# Carte_MiniPAMI_2025.net
KiCad netlist of a schematic drawn in Altium Designer
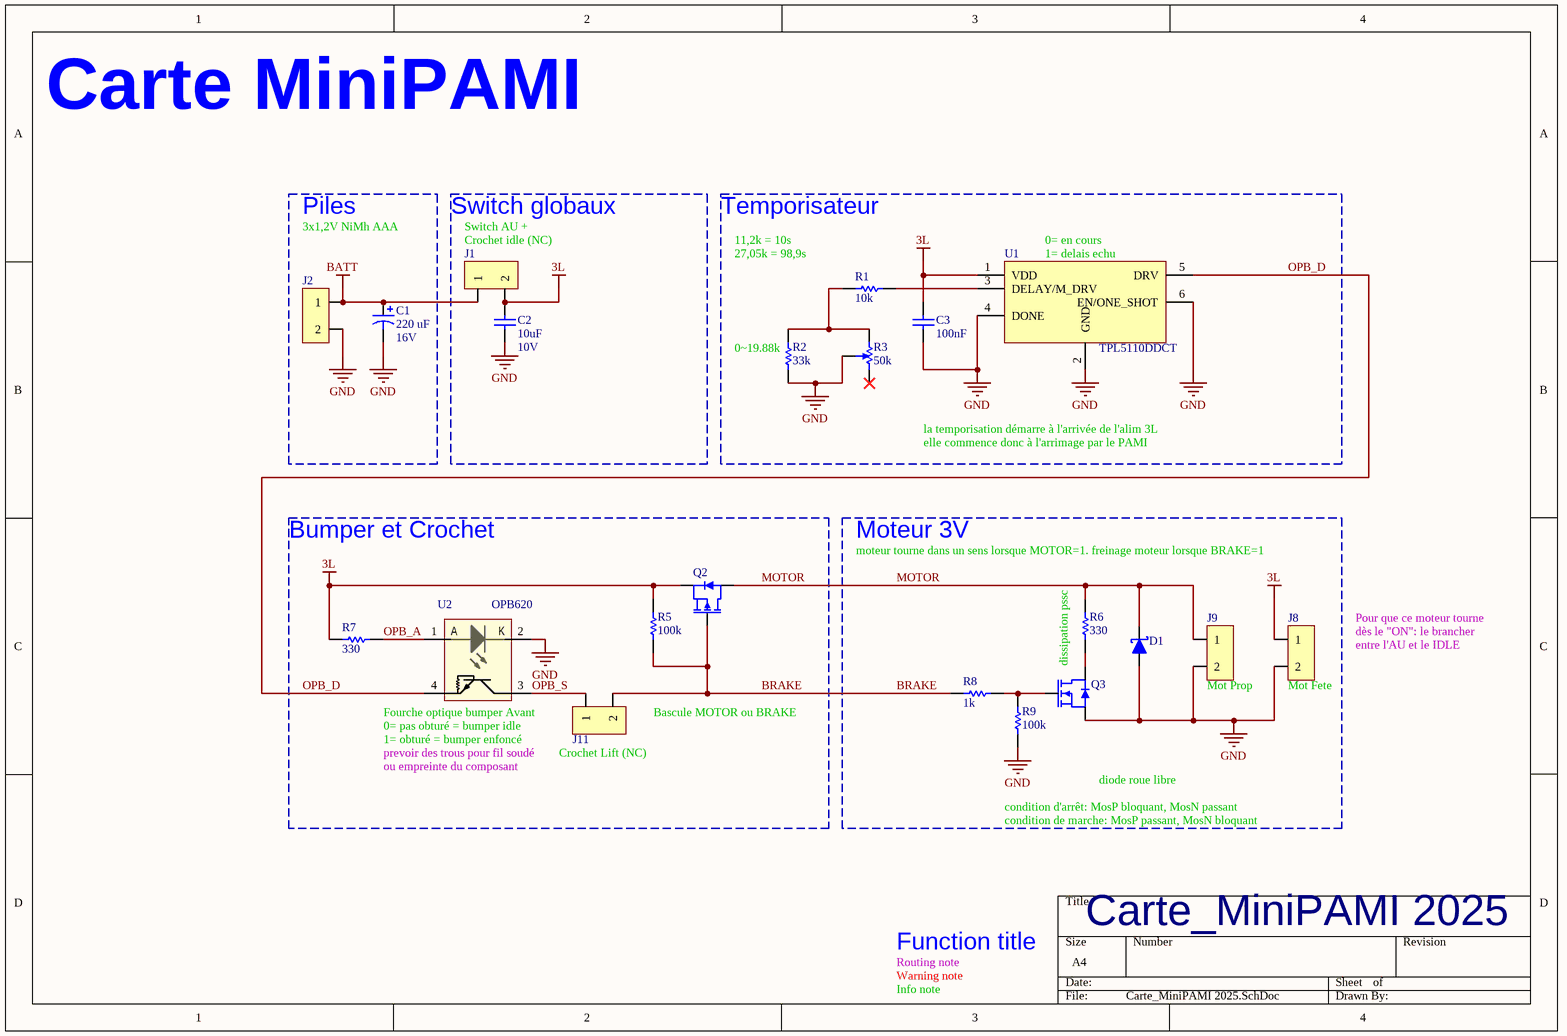
[diagram p0: Carte_MiniPAMI 2025.SchDoc]

(export (version "E")
  (design (tool "Eeschema 10.0.6"))
  (components
    (comp (ref "C1")
      (value "220 uF")
      (footprint "WCAP-ATG8_6.3x11x2.5x0.5")
      (description "CAP Alu 220 UF 20% 16 V")
      (fields
        (field (name "MANUFACTURER") "Wurth Elektronik")
        (field (name "MANUFACTURER PART NUMBER") "860010373010")
        (field (name "RATEDVOLTAGE") "16V")
      )
      (libsource (lib "Condensateur") (part "WCAP-ATG8, 860010373010"))
    )
    (comp (ref "C2")
      (value "10uF")
      (footprint "WCAP-CSGP_0805, 2x1.25x1.25")
      (description "CAP CER 10uF 10V X7R 0805")
      (fields
        (field (name "RATEDVOLTAGE") "10V")
        (field (name "MANUFACTURER") "Wurth Elektronik")
        (field (name "MANUFACTURER PART NUMBER") "885012207026")
      )
      (libsource (lib "Condensateur") (part "WCAP-CSGP, 885012207026"))
    )
    (comp (ref "C3")
      (value "100nF")
      (footprint "WCAP-CSGP_0603, 1.6x0.8x0.8")
      (description "CAP CER 100nF 50V X7R 0603")
      (fields
        (field (name "MANUFACTURER") "Wurth Elektronik")
        (field (name "MANUFACTURER PART NUMBER") "885012206095")
      )
      (libsource (lib "Condensateur") (part "WCAP-CSGP, 885012206095"))
    )
    (comp (ref "D1")
      (value "RBR3MM40ATFTR")
      (footprint "SOD-123FL")
      (description "DIODE SCHOTTKY 40V 3A SOD123-FL")
      (fields (field (name "MANUFACTURER") "ROHM"))
      (libsource (lib "Diode") (part "RBR3MM40ATFTR"))
    )
    (comp (ref "J1")
      (value "22-03-2021")
      (footprint "Conn_22-03-2021")
      (description "CONN HEADER VERT 2POS 2.54MM")
      (fields (field (name "MANUFACTURER") "MOLEX"))
      (libsource (lib "") (part "Conn_22-03-2021_1"))
    )
    (comp (ref "J2")
      (value "22-03-2021")
      (footprint "Conn_22-03-2021")
      (description "CONN HEADER VERT 2POS 2.54MM")
      (fields (field (name "MANUFACTURER") "MOLEX"))
      (libsource (lib "") (part "Conn_22-03-2021_3"))
    )
    (comp (ref "J8")
      (value "22-03-2021")
      (footprint "Conn_22-03-2021")
      (description "CONN HEADER VERT 2POS 2.54MM")
      (fields (field (name "MANUFACTURER") "MOLEX"))
      (libsource (lib "Connecteurs") (part "Conn_22-03-2021"))
    )
    (comp (ref "J9")
      (value "22-03-2021")
      (footprint "Conn_22-03-2021")
      (description "CONN HEADER VERT 2POS 2.54MM")
      (fields (field (name "MANUFACTURER") "MOLEX"))
      (libsource (lib "Connecteurs") (part "Conn_22-03-2021"))
    )
    (comp (ref "J11")
      (value "22-03-2021")
      (footprint "Conn_22-03-2021")
      (description "CONN HEADER VERT 2POS 2.54MM")
      (fields (field (name "MANUFACTURER") "MOLEX"))
      (libsource (lib "") (part "Conn_22-03-2021_2"))
    )
    (comp (ref "Q2")
      (value "ZXM61P03FTA")
      (footprint "SOT-23")
      (description "MOSFET P-CH 30V 1.1A SOT23-3")
      (fields (field (name "MANUFACTURER") "Diodes Incorporated"))
      (libsource (lib "Transistors") (part "ZXM61P03FTA"))
    )
    (comp (ref "Q3")
      (value "IRLML0040TRPBF")
      (footprint "SOT-23")
      (description "MOSFET N 40V 3.6A SOT23")
      (fields (field (name "MANUFACTURER") "INTERNATIONAL RECTIFIER"))
      (libsource (lib "Transistors") (part "IRLML0040"))
    )
    (comp (ref "R1")
      (value "10k")
      (footprint "RESC1608X06N")
      (description "RES SMD 10K OHM 1% 1/10W 0603")
      (fields
        (field (name "MANUFACTURER") "Yageo")
        (field (name "MANUFACTURER PART NUMBER") "RC0603FR-0710KL")
      )
      (libsource (lib "Resistance") (part "RC0603FR-0710KL"))
    )
    (comp (ref "R2")
      (value "33k")
      (footprint "RESC1608X06N")
      (description "RES SMD 33K OHM 1% 1/10W 0603")
      (fields (field (name "MANUFACTURER") "Yageo") (field (name "POWER") "100mW"))
      (libsource (lib "Resistance") (part "RC0603FR-0710KL"))
    )
    (comp (ref "R3")
      (value "50k")
      (footprint "TRIM_PANASONIC_EVM-2W")
      (description "TRIMMER 50K OHM 0.15W SMD")
      (fields
        (field (name "MANUFACTURER") "PANASONIC ELECTRONIC COMPONENTS")
        (field (name "MANUFACTURER PART NUMBER") "EVM2WSX80B54")
      )
      (libsource (lib "Resistance") (part "EVM2WSX80B54"))
    )
    (comp (ref "R5")
      (value "100k")
      (footprint "RESC1608X06N")
      (description "RES SMD 100K OHM 1% 1/10W 0603")
      (fields
        (field (name "MANUFACTURER") "Yageo")
        (field (name "MANUFACTURER PART NUMBER") "RC0603FR-07100KL")
      )
      (libsource (lib "Resistance") (part "RC0603FR-07100KL"))
    )
    (comp (ref "R6")
      (value "330")
      (footprint "RESC1608X06N")
      (description "RES SMD 330 OHM 1% 1/10W 0603")
      (fields
        (field (name "MANUFACTURER") "Yageo")
        (field (name "MANUFACTURER PART NUMBER") "RC0603FR-07330RL")
      )
      (libsource (lib "Resistance") (part "RC0603FR-07330RL"))
    )
    (comp (ref "R7")
      (value "330")
      (footprint "RESC1608X06N")
      (description "RES SMD 330 OHM 1% 1/10W 0603")
      (fields
        (field (name "MANUFACTURER") "Yageo")
        (field (name "MANUFACTURER PART NUMBER") "RC0603FR-07330RL")
      )
      (libsource (lib "Resistance") (part "RC0603FR-07330RL"))
    )
    (comp (ref "R8")
      (value "1k")
      (footprint "RESC1608X06N")
      (description "RES SMD 1K OHM 1% 1/10W 0603")
      (fields
        (field (name "MANUFACTURER") "Yageo")
        (field (name "MANUFACTURER PART NUMBER") "RC0603FR-071KL")
      )
      (libsource (lib "Resistance") (part "RC0603FR-071KL"))
    )
    (comp (ref "R9")
      (value "100k")
      (footprint "RESC1608X06N")
      (description "RES SMD 100K OHM 1% 1/10W 0603")
      (fields
        (field (name "MANUFACTURER") "Yageo")
        (field (name "MANUFACTURER PART NUMBER") "RC0603FR-07100KL")
      )
      (libsource (lib "Resistance") (part "RC0603FR-07100KL"))
    )
    (comp (ref "U1")
      (value "TPL5110DDCT")
      (footprint "SOT23_95P280X145-6N")
      (description "IC OSC PROG TIMER TSOT23-6")
      (fields (field (name "MANUFACTURER") "TEXAS INSTRUMENTS"))
      (libsource (lib "CI") (part "TPL5110DDCT"))
    )
    (comp (ref "U2")
      (value "OPB620")
      (footprint "OPB620")
      (description "SENSOR OPT SLOT TRANS W/RES PCB")
      (fields (field (name "MANUFACTURER") "TT ELECTRONICS"))
      (libsource (lib "Opto") (part "OPB620"))
    )
  )
  (nets
    (net (code "1") (name "/BRAKE") (class "Default")
      (node (ref "J11") (pin "2") (pinfunction "2_2") (pintype "passive"))
      (node (ref "Q2") (pin "1") (pinfunction "G_1") (pintype "passive"))
      (node (ref "R5") (pin "1") (pinfunction "1_1") (pintype "passive"))
      (node (ref "R8") (pin "2") (pinfunction "2_2") (pintype "passive"))
    )
    (net (code "2") (name "/MOTOR") (class "Default")
      (node (ref "D1") (pin "2") (pintype "passive"))
      (node (ref "J9") (pin "1") (pinfunction "1_1") (pintype "passive"))
      (node (ref "Q2") (pin "3") (pinfunction "D_3") (pintype "passive"))
      (node (ref "R6") (pin "2") (pinfunction "2_2") (pintype "passive"))
    )
    (net (code "3") (name "/OPB_A") (class "Default")
      (node (ref "R7") (pin "2") (pinfunction "2_2") (pintype "passive"))
      (node (ref "U2") (pin "1") (pinfunction "LED_A_1") (pintype "passive"))
    )
    (net (code "4") (name "/OPB_D") (class "Default")
      (node (ref "U1") (pin "5") (pinfunction "DRV_5") (pintype "passive"))
      (node (ref "U2") (pin "4") (pinfunction "NPN_E_4") (pintype "passive"))
    )
    (net (code "5") (name "/OPB_S") (class "Default")
      (node (ref "J11") (pin "1") (pinfunction "1_1") (pintype "passive"))
      (node (ref "U2") (pin "3") (pinfunction "NPN_C_3") (pintype "passive"))
    )
    (net (code "6") (name "3L") (class "Default")
      (node (ref "C2") (pin "1") (pinfunction "1_1") (pintype "passive"))
      (node (ref "C3") (pin "1") (pinfunction "1_1") (pintype "passive"))
      (node (ref "J1") (pin "2") (pinfunction "2_2") (pintype "passive"))
      (node (ref "J8") (pin "1") (pinfunction "1_1") (pintype "passive"))
      (node (ref "Q2") (pin "2") (pinfunction "S_2") (pintype "passive"))
      (node (ref "R5") (pin "2") (pinfunction "2_2") (pintype "passive"))
      (node (ref "R7") (pin "1") (pinfunction "1_1") (pintype "passive"))
      (node (ref "U1") (pin "1") (pinfunction "VDD_1") (pintype "passive"))
    )
    (net (code "7") (name "BATT") (class "Default")
      (node (ref "C1") (pin "1") (pinfunction "1_1") (pintype "passive"))
      (node (ref "J1") (pin "1") (pinfunction "1_1") (pintype "passive"))
      (node (ref "J2") (pin "1") (pinfunction "1_1") (pintype "passive"))
    )
    (net (code "8") (name "GND") (class "Default")
      (node (ref "C1") (pin "2") (pinfunction "2_2") (pintype "passive"))
      (node (ref "C2") (pin "2") (pinfunction "2_2") (pintype "passive"))
      (node (ref "C3") (pin "2") (pinfunction "2_2") (pintype "passive"))
      (node (ref "D1") (pin "1") (pintype "passive"))
      (node (ref "J2") (pin "2") (pinfunction "2_2") (pintype "passive"))
      (node (ref "J8") (pin "2") (pinfunction "2_2") (pintype "passive"))
      (node (ref "J9") (pin "2") (pinfunction "2_2") (pintype "passive"))
      (node (ref "Q3") (pin "2") (pinfunction "S_2") (pintype "passive"))
      (node (ref "R2") (pin "2") (pinfunction "2_2") (pintype "passive"))
      (node (ref "R3") (pin "2") (pintype "passive"))
      (node (ref "R9") (pin "1") (pinfunction "1_1") (pintype "passive"))
      (node (ref "U1") (pin "2") (pinfunction "GND_2") (pintype "passive"))
      (node (ref "U1") (pin "4") (pinfunction "DONE_4") (pintype "passive"))
      (node (ref "U1") (pin "6") (pinfunction "EN/ONE_SHOT_6") (pintype "passive"))
      (node (ref "U2") (pin "2") (pinfunction "LED_K_2") (pintype "passive"))
    )
    (net (code "9") (name "Net-(Q3-D)") (class "Default")
      (node (ref "Q3") (pin "3") (pinfunction "D_3") (pintype "passive"))
      (node (ref "R6") (pin "1") (pinfunction "1_1") (pintype "passive"))
    )
    (net (code "10") (name "Net-(Q3-G)") (class "Default")
      (node (ref "Q3") (pin "1") (pinfunction "G_1") (pintype "passive"))
      (node (ref "R8") (pin "1") (pinfunction "1_1") (pintype "passive"))
      (node (ref "R9") (pin "2") (pinfunction "2_2") (pintype "passive"))
    )
    (net (code "11") (name "Net-(R1-Pad1)") (class "Default")
      (node (ref "R1") (pin "1") (pinfunction "1_1") (pintype "passive"))
      (node (ref "R2") (pin "1") (pinfunction "1_1") (pintype "passive"))
      (node (ref "R3") (pin "1") (pintype "passive"))
    )
    (net (code "12") (name "Net-(U1-DELAY{slash}M_DRV)") (class "Default")
      (node (ref "R1") (pin "2") (pinfunction "2_2") (pintype "passive"))
      (node (ref "U1") (pin "3") (pinfunction "DELAY/M_DRV_3") (pintype "passive"))
    )
    (net (code "13") (name "unconnected-(R3-Pad3)") (class "Default")
      (node (ref "R3") (pin "3") (pintype "passive+no_connect"))
    )
  )
)
